# Arduino_pro_micro_sch.net
KiCad netlist of a schematic drawn in EasyEDA
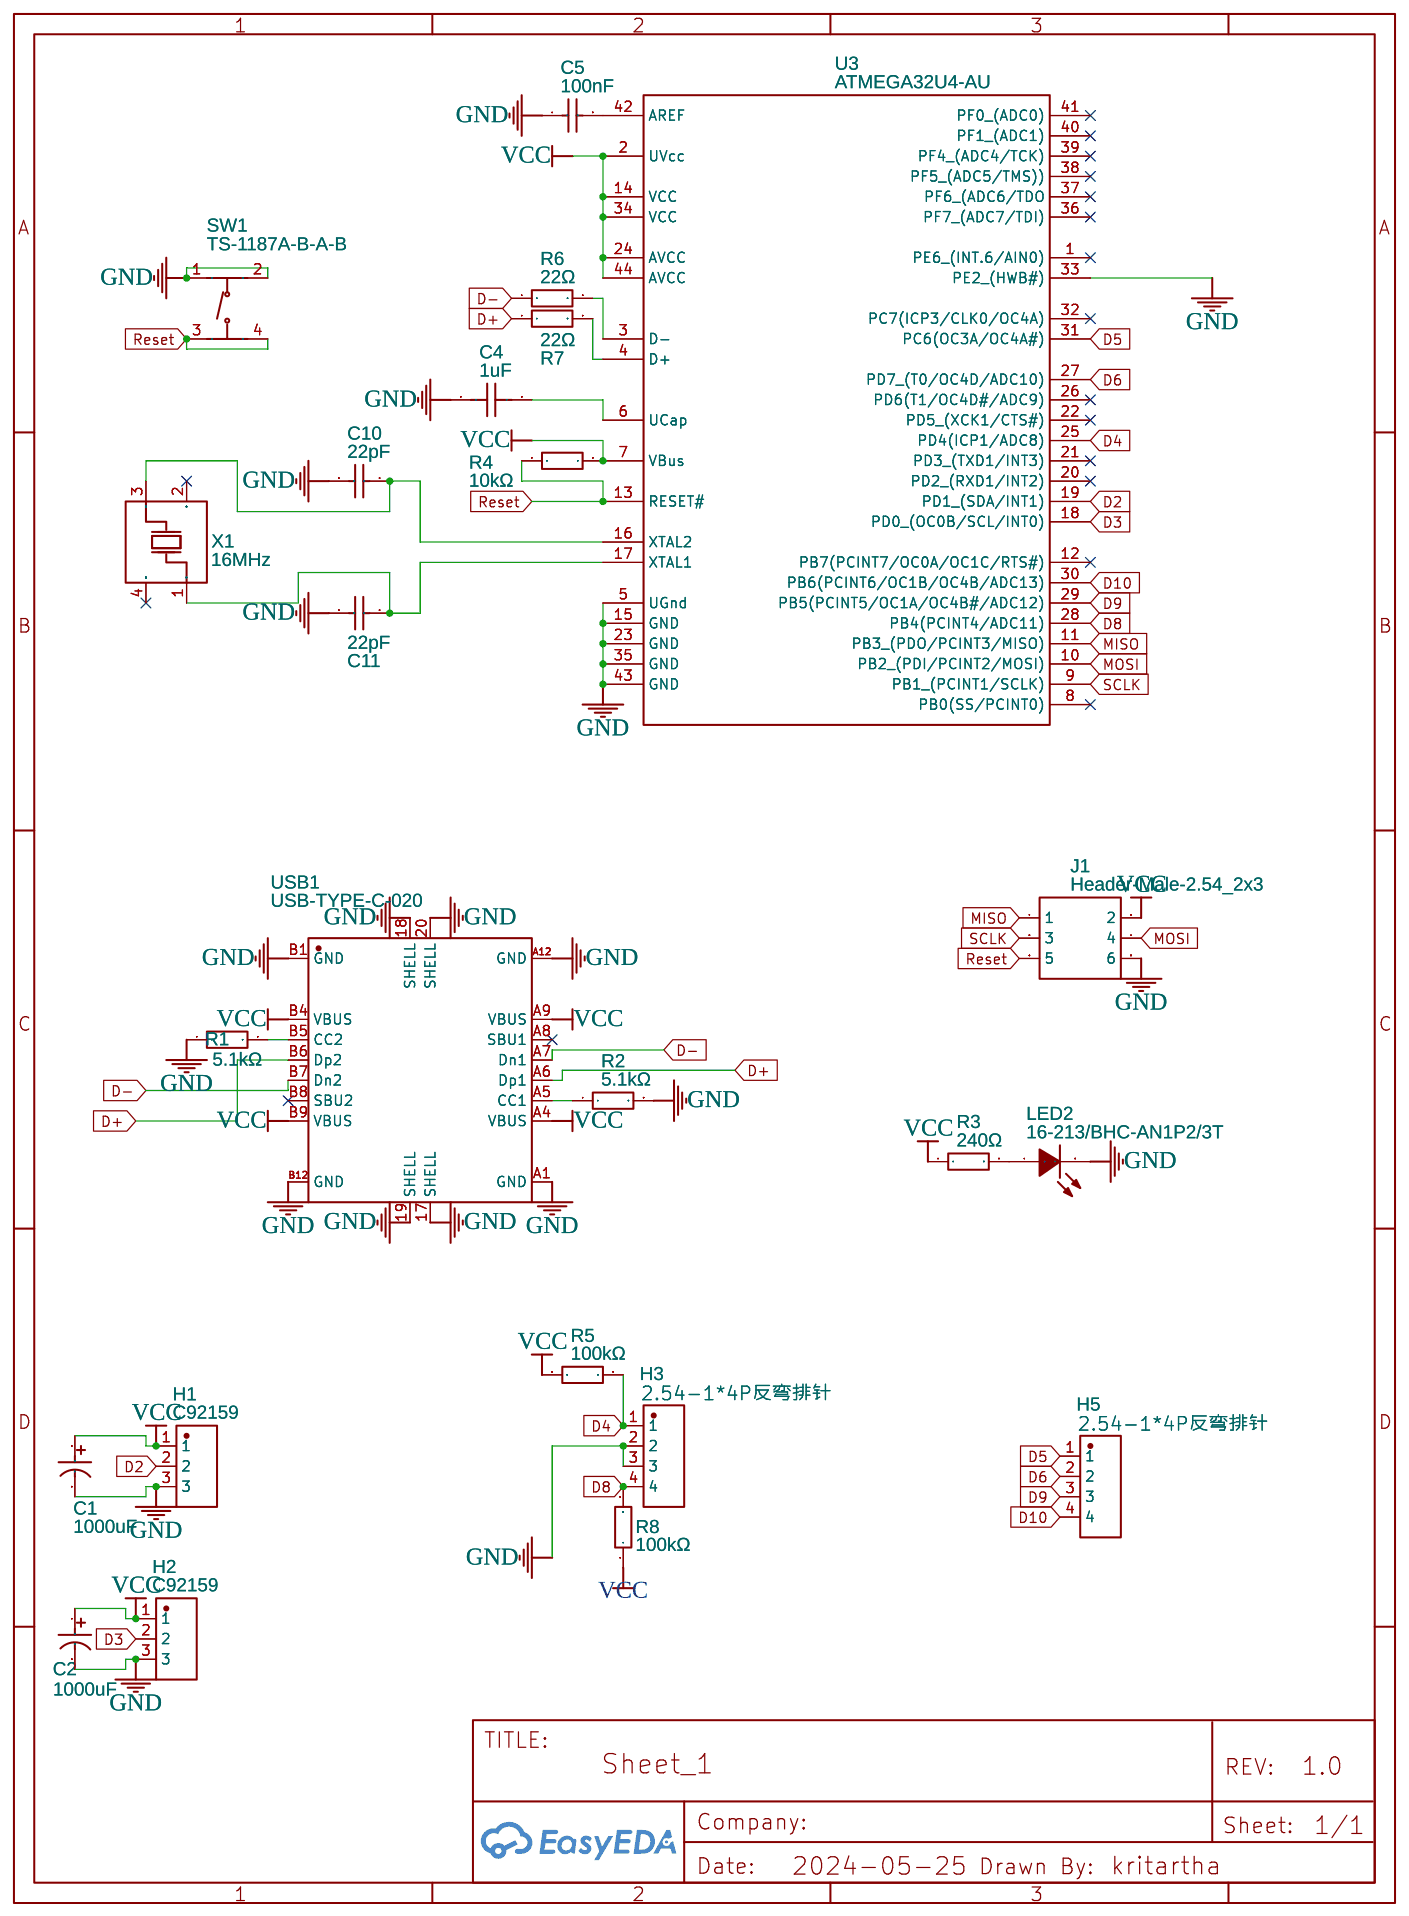
[diagram p0: schematic sheet]

(export (version "E")
  (design (tool "Eeschema 10.0.6"))
  (components
    (comp (ref "C1")
      (value "1000uF")
      (fields (field (name "Manufacturer Part") "RVT1C102M1010") (field (name "Manufacturer") "HONOR(荣誉)"))
      (libsource (lib "") (part "RVT1C102M1010_C3359"))
    )
    (comp (ref "C2")
      (value "1000uF")
      (fields (field (name "Manufacturer Part") "RVT1C102M1010") (field (name "Manufacturer") "HONOR(荣誉)"))
      (libsource (lib "") (part "RVT1C102M1010_C3359"))
    )
    (comp (ref "C4")
      (value "1uF")
      (fields
        (field (name "Manufacturer Part") "CL05A105KA5NQNC")
        (field (name "Manufacturer") "SAMSUNG(三星)")
      )
      (libsource (lib "") (part "CL05A105KA5NQNC"))
    )
    (comp (ref "C5")
      (value "100nF")
      (fields
        (field (name "Manufacturer Part") "CL05B104KO5NNNC")
        (field (name "Manufacturer") "SAMSUNG(三星)")
      )
      (libsource (lib "") (part "CL05B104KO5NNNC"))
    )
    (comp (ref "C10")
      (value "22pF")
      (fields (field (name "Manufacturer Part") "0402CG220J500NT") (field (name "Manufacturer") "FH(风华)"))
      (libsource (lib "") (part "0402CG220J500NT_1"))
    )
    (comp (ref "C11")
      (value "22pF")
      (fields (field (name "Manufacturer Part") "0402CG220J500NT") (field (name "Manufacturer") "FH(风华)"))
      (libsource (lib "") (part "0402CG220J500NT"))
    )
    (comp (ref "H1")
      (value "C92159")
      (fields (field (name "Manufacturer Part") "2.54-1*3P正弯针") (field (name "Manufacturer") "BOOMELE(博穆精密)"))
      (libsource (lib "") (part "C92159"))
    )
    (comp (ref "H2")
      (value "C92159")
      (fields (field (name "Manufacturer Part") "2.54-1*3P正弯针") (field (name "Manufacturer") "BOOMELE(博穆精密)"))
      (libsource (lib "") (part "C92159"))
    )
    (comp (ref "H3")
      (value "2.54-1*4P反弯排针")
      (fields (field (name "Manufacturer") "BOOMELE(博穆精密)"))
      (libsource (lib "") (part "2.54-1*4P反弯排针"))
    )
    (comp (ref "H5")
      (value "2.54-1*4P反弯排针")
      (fields (field (name "Manufacturer") "BOOMELE(博穆精密)"))
      (libsource (lib "") (part "2.54-1*4P反弯排针"))
    )
    (comp (ref "J1")
      (value "Header-Male-2.54_2x3")
      (fields (field (name "Manufacturer Part") "2.54-2*3P针") (field (name "Manufacturer") "BOOMELE(博穆精密)"))
      (libsource (lib "") (part "Header-Male-2.54_2x3"))
    )
    (comp (ref "LED2")
      (value "16-213/BHC-AN1P2/3T")
      (fields (field (name "Manufacturer") "EVERLIGHT(亿光)"))
      (libsource (lib "") (part "16-213/BHC-AN1P2/3T"))
    )
    (comp (ref "R1")
      (value "5.1kΩ")
      (fields
        (field (name "Manufacturer Part") "0402WGF5101TCE")
        (field (name "Manufacturer") "UNI-ROYAL(厚声)")
      )
      (libsource (lib "") (part "0402WGF5101TCE"))
    )
    (comp (ref "R2")
      (value "5.1kΩ")
      (fields
        (field (name "Manufacturer Part") "0402WGF5101TCE")
        (field (name "Manufacturer") "UNI-ROYAL(厚声)")
      )
      (libsource (lib "") (part "0402WGF5101TCE"))
    )
    (comp (ref "R3")
      (value "240Ω")
      (fields (field (name "Manufacturer Part") "RS-03K2400FT") (field (name "Manufacturer") "FH(风华)"))
      (libsource (lib "") (part "RS-03K2400FT"))
    )
    (comp (ref "R4")
      (value "10kΩ")
      (fields
        (field (name "Manufacturer Part") "0402WGF1002TCE")
        (field (name "Manufacturer") "UNI-ROYAL(厚声)")
      )
      (libsource (lib "") (part "0402WGF1002TCE"))
    )
    (comp (ref "R5")
      (value "100kΩ")
      (fields
        (field (name "Manufacturer Part") "0402WGF1003TCE")
        (field (name "Manufacturer") "UNI-ROYAL(厚声)")
      )
      (libsource (lib "") (part "0402WGF1003TCE"))
    )
    (comp (ref "R6")
      (value "22Ω")
      (fields
        (field (name "Manufacturer Part") "0402WGF220JTCE")
        (field (name "Manufacturer") "UNI-ROYAL(厚声)")
      )
      (libsource (lib "") (part "0402WGF220JTCE"))
    )
    (comp (ref "R7")
      (value "22Ω")
      (fields
        (field (name "Manufacturer Part") "0402WGF220JTCE")
        (field (name "Manufacturer") "UNI-ROYAL(厚声)")
      )
      (libsource (lib "") (part "0402WGF220JTCE"))
    )
    (comp (ref "R8")
      (value "100kΩ")
      (fields
        (field (name "Manufacturer Part") "0402WGF1003TCE")
        (field (name "Manufacturer") "UNI-ROYAL(厚声)")
      )
      (libsource (lib "") (part "0402WGF1003TCE_1"))
    )
    (comp (ref "SW1")
      (value "TS-1187A-B-A-B")
      (fields (field (name "Manufacturer") "XKB Connectivity(中国星坤)"))
      (libsource (lib "") (part "TS-1187A-B-A-B"))
    )
    (comp (ref "U3")
      (value "ATMEGA32U4-AU")
      (fields (field (name "Manufacturer") "MICROCHIP(美国微芯)"))
      (libsource (lib "") (part "ATMEGA32U4-AU"))
    )
    (comp (ref "USB1")
      (value "USB-TYPE-C-020")
      (fields (field (name "Manufacturer") "DEALON(德艺隆)"))
      (libsource (lib "") (part "USB-TYPE-C-020"))
    )
    (comp (ref "X1")
      (value "16MHz")
      (fields (field (name "Manufacturer Part") "X322516MLB4SI") (field (name "Manufacturer") "YXC(扬兴晶振)"))
      (libsource (lib "") (part "X322516MLB4SI"))
    )
  )
  (nets
    (net (code "1") (name "D+") (class "Default")
      (node (ref "R7") (pin "1") (pinfunction "1_1") (pintype "input"))
      (node (ref "USB1") (pin "A6") (pinfunction "Dp1_A6") (pintype "unspecified"))
      (node (ref "USB1") (pin "B6") (pinfunction "Dp2_B6") (pintype "unspecified"))
    )
    (net (code "2") (name "D-") (class "Default")
      (node (ref "R6") (pin "1") (pinfunction "1_1") (pintype "input"))
      (node (ref "USB1") (pin "A7") (pinfunction "Dn1_A7") (pintype "unspecified"))
      (node (ref "USB1") (pin "B7") (pinfunction "Dn2_B7") (pintype "unspecified"))
    )
    (net (code "3") (name "D2") (class "Default")
      (node (ref "H1") (pin "2") (pinfunction "2_2") (pintype "unspecified"))
      (node (ref "U3") (pin "19") (pinfunction "PD1_(SDA/INT1)_19") (pintype "bidirectional"))
    )
    (net (code "4") (name "D3") (class "Default")
      (node (ref "H2") (pin "2") (pinfunction "2_2") (pintype "unspecified"))
      (node (ref "U3") (pin "18") (pinfunction "PD0_(OC0B/SCL/INT0)_18") (pintype "bidirectional"))
    )
    (net (code "5") (name "D4") (class "Default")
      (node (ref "H3") (pin "1") (pinfunction "1_1") (pintype "unspecified"))
      (node (ref "R5") (pin "1") (pinfunction "1_1") (pintype "input"))
      (node (ref "U3") (pin "25") (pinfunction "PD4(ICP1/ADC8)_25") (pintype "bidirectional"))
    )
    (net (code "6") (name "D5") (class "Default")
      (node (ref "H5") (pin "1") (pinfunction "1_1") (pintype "unspecified"))
      (node (ref "U3") (pin "31") (pinfunction "PC6(OC3A/OC4A#)_31") (pintype "bidirectional"))
    )
    (net (code "7") (name "D6") (class "Default")
      (node (ref "H5") (pin "2") (pinfunction "2_2") (pintype "unspecified"))
      (node (ref "U3") (pin "27") (pinfunction "PD7_(T0/OC4D/ADC10)_27") (pintype "bidirectional"))
    )
    (net (code "8") (name "D8") (class "Default")
      (node (ref "H3") (pin "4") (pinfunction "4_4") (pintype "unspecified"))
      (node (ref "R8") (pin "2") (pinfunction "2_2") (pintype "input"))
      (node (ref "U3") (pin "28") (pinfunction "PB4(PCINT4/ADC11)_28") (pintype "bidirectional"))
    )
    (net (code "9") (name "D9") (class "Default")
      (node (ref "H5") (pin "3") (pinfunction "3_3") (pintype "unspecified"))
      (node (ref "U3") (pin "29") (pinfunction "PB5(PCINT5/OC1A/OC4B#/ADC12)_29") (pintype "bidirectional"))
    )
    (net (code "10") (name "D10") (class "Default")
      (node (ref "H5") (pin "4") (pinfunction "4_4") (pintype "unspecified"))
      (node (ref "U3") (pin "30") (pinfunction "PB6(PCINT6/OC1B/OC4B/ADC13)_30") (pintype "bidirectional"))
    )
    (net (code "11") (name "GND") (class "Default")
      (node (ref "C1") (pin "2") (pinfunction "2_2") (pintype "input"))
      (node (ref "C10") (pin "1") (pinfunction "1_1") (pintype "input"))
      (node (ref "C11") (pin "1") (pinfunction "1_1") (pintype "input"))
      (node (ref "C2") (pin "2") (pinfunction "2_2") (pintype "input"))
      (node (ref "C4") (pin "1") (pinfunction "1_1") (pintype "unspecified"))
      (node (ref "C5") (pin "1") (pinfunction "1_1") (pintype "input"))
      (node (ref "H1") (pin "3") (pinfunction "3_3") (pintype "unspecified"))
      (node (ref "H2") (pin "3") (pinfunction "3_3") (pintype "unspecified"))
      (node (ref "H3") (pin "2") (pinfunction "2_2") (pintype "unspecified"))
      (node (ref "H3") (pin "3") (pinfunction "3_3") (pintype "unspecified"))
      (node (ref "J1") (pin "6") (pinfunction "6_6") (pintype "input"))
      (node (ref "LED2") (pin "2") (pinfunction "K_2") (pintype "unspecified"))
      (node (ref "R1") (pin "1") (pinfunction "1_1") (pintype "input"))
      (node (ref "R2") (pin "2") (pinfunction "2_2") (pintype "input"))
      (node (ref "SW1") (pin "1") (pinfunction "A_1") (pintype "unspecified"))
      (node (ref "SW1") (pin "2") (pinfunction "B_2") (pintype "unspecified"))
      (node (ref "U3") (pin "15") (pinfunction "GND_15") (pintype "passive"))
      (node (ref "U3") (pin "23") (pinfunction "GND_23") (pintype "passive"))
      (node (ref "U3") (pin "33") (pinfunction "PE2_(HWB#)_33") (pintype "bidirectional"))
      (node (ref "U3") (pin "35") (pinfunction "GND_35") (pintype "passive"))
      (node (ref "U3") (pin "43") (pinfunction "GND_43") (pintype "passive"))
      (node (ref "U3") (pin "5") (pinfunction "UGnd_5") (pintype "passive"))
      (node (ref "USB1") (pin "17") (pinfunction "SHELL_17") (pintype "unspecified"))
      (node (ref "USB1") (pin "18") (pinfunction "SHELL_18") (pintype "unspecified"))
      (node (ref "USB1") (pin "19") (pinfunction "SHELL_19") (pintype "unspecified"))
      (node (ref "USB1") (pin "20") (pinfunction "SHELL_20") (pintype "unspecified"))
      (node (ref "USB1") (pin "A1") (pinfunction "GND_A1") (pintype "unspecified"))
      (node (ref "USB1") (pin "A12") (pinfunction "GND_A12") (pintype "unspecified"))
      (node (ref "USB1") (pin "B1") (pinfunction "GND_B1") (pintype "unspecified"))
      (node (ref "USB1") (pin "B12") (pinfunction "GND_B12") (pintype "unspecified"))
    )
    (net (code "12") (name "MISO") (class "Default")
      (node (ref "J1") (pin "1") (pinfunction "1_1") (pintype "input"))
      (node (ref "U3") (pin "11") (pinfunction "PB3_(PDO/PCINT3/MISO)_11") (pintype "bidirectional"))
    )
    (net (code "13") (name "MOSI") (class "Default")
      (node (ref "J1") (pin "4") (pinfunction "4_4") (pintype "input"))
      (node (ref "U3") (pin "10") (pinfunction "PB2_(PDI/PCINT2/MOSI)_10") (pintype "bidirectional"))
    )
    (net (code "14") (name "Net-(LED2-A)") (class "Default")
      (node (ref "LED2") (pin "1") (pinfunction "A_1") (pintype "unspecified"))
      (node (ref "R3") (pin "2") (pinfunction "2_2") (pintype "unspecified"))
    )
    (net (code "15") (name "Net-(U3-AREF)") (class "Default")
      (node (ref "C5") (pin "2") (pinfunction "2_2") (pintype "input"))
      (node (ref "U3") (pin "42") (pinfunction "AREF_42") (pintype "unspecified"))
    )
    (net (code "16") (name "Net-(U3-D+)") (class "Default")
      (node (ref "R7") (pin "2") (pinfunction "2_2") (pintype "input"))
      (node (ref "U3") (pin "4") (pinfunction "D+_4") (pintype "bidirectional"))
    )
    (net (code "17") (name "Net-(U3-D-)") (class "Default")
      (node (ref "R6") (pin "2") (pinfunction "2_2") (pintype "input"))
      (node (ref "U3") (pin "3") (pinfunction "D-_3") (pintype "bidirectional"))
    )
    (net (code "18") (name "Net-(U3-UCap)") (class "Default")
      (node (ref "C4") (pin "2") (pinfunction "2_2") (pintype "unspecified"))
      (node (ref "U3") (pin "6") (pinfunction "UCap_6") (pintype "unspecified"))
    )
    (net (code "19") (name "Net-(U3-XTAL1)") (class "Default")
      (node (ref "C11") (pin "2") (pinfunction "2_2") (pintype "input"))
      (node (ref "U3") (pin "17") (pinfunction "XTAL1_17") (pintype "unspecified"))
      (node (ref "X1") (pin "1") (pinfunction "OSC1_1") (pintype "unspecified"))
    )
    (net (code "20") (name "Net-(U3-XTAL2)") (class "Default")
      (node (ref "C10") (pin "2") (pinfunction "2_2") (pintype "input"))
      (node (ref "U3") (pin "16") (pinfunction "XTAL2_16") (pintype "output"))
      (node (ref "X1") (pin "3") (pinfunction "OSC2_3") (pintype "unspecified"))
    )
    (net (code "21") (name "Net-(USB1-CC1)") (class "Default")
      (node (ref "R2") (pin "1") (pinfunction "1_1") (pintype "input"))
      (node (ref "USB1") (pin "A5") (pinfunction "CC1_A5") (pintype "unspecified"))
    )
    (net (code "22") (name "Net-(USB1-CC2)") (class "Default")
      (node (ref "R1") (pin "2") (pinfunction "2_2") (pintype "input"))
      (node (ref "USB1") (pin "B5") (pinfunction "CC2_B5") (pintype "unspecified"))
    )
    (net (code "23") (name "Reset") (class "Default")
      (node (ref "J1") (pin "5") (pinfunction "5_5") (pintype "input"))
      (node (ref "R4") (pin "1") (pinfunction "1_1") (pintype "input"))
      (node (ref "SW1") (pin "3") (pinfunction "C_3") (pintype "unspecified"))
      (node (ref "SW1") (pin "4") (pinfunction "D_4") (pintype "unspecified"))
      (node (ref "U3") (pin "13") (pinfunction "RESET#_13") (pintype "unspecified"))
    )
    (net (code "24") (name "SCLK") (class "Default")
      (node (ref "J1") (pin "3") (pinfunction "3_3") (pintype "input"))
      (node (ref "U3") (pin "9") (pinfunction "PB1_(PCINT1/SCLK)_9") (pintype "bidirectional"))
    )
    (net (code "25") (name "VCC") (class "Default")
      (node (ref "C1") (pin "1") (pinfunction "1_1") (pintype "input"))
      (node (ref "C2") (pin "1") (pinfunction "1_1") (pintype "input"))
      (node (ref "H1") (pin "1") (pinfunction "1_1") (pintype "unspecified"))
      (node (ref "H2") (pin "1") (pinfunction "1_1") (pintype "unspecified"))
      (node (ref "J1") (pin "2") (pinfunction "2_2") (pintype "input"))
      (node (ref "R3") (pin "1") (pinfunction "1_1") (pintype "unspecified"))
      (node (ref "R4") (pin "2") (pinfunction "2_2") (pintype "input"))
      (node (ref "R5") (pin "2") (pinfunction "2_2") (pintype "input"))
      (node (ref "R8") (pin "1") (pinfunction "1_1") (pintype "input"))
      (node (ref "U3") (pin "14") (pinfunction "VCC_14") (pintype "passive"))
      (node (ref "U3") (pin "2") (pinfunction "UVcc_2") (pintype "passive"))
      (node (ref "U3") (pin "24") (pinfunction "AVCC_24") (pintype "passive"))
      (node (ref "U3") (pin "34") (pinfunction "VCC_34") (pintype "passive"))
      (node (ref "U3") (pin "44") (pinfunction "AVCC_44") (pintype "passive"))
      (node (ref "U3") (pin "7") (pinfunction "VBus_7") (pintype "unspecified"))
      (node (ref "USB1") (pin "A4") (pinfunction "VBUS_A4") (pintype "unspecified"))
      (node (ref "USB1") (pin "A9") (pinfunction "VBUS_A9") (pintype "unspecified"))
      (node (ref "USB1") (pin "B4") (pinfunction "VBUS_B4") (pintype "unspecified"))
      (node (ref "USB1") (pin "B9") (pinfunction "VBUS_B9") (pintype "unspecified"))
    )
    (net (code "26") (name "unconnected-(U3-PB0(SS{slash}PCINT0)-Pad8)") (class "Default")
      (node (ref "U3") (pin "8") (pinfunction "PB0(SS/PCINT0)_8") (pintype "bidirectional+no_connect"))
    )
    (net (code "27") (name "unconnected-(U3-PB7(PCINT7{slash}OC0A{slash}OC1C{slash}RTS#)-Pad12)") (class "Default")
      (node (ref "U3") (pin "12") (pinfunction "PB7(PCINT7/OC0A/OC1C/RTS#)_12") (pintype "bidirectional+no_connect"))
    )
    (net (code "28") (name "unconnected-(U3-PC7(ICP3{slash}CLK0{slash}OC4A)-Pad32)") (class "Default")
      (node (ref "U3") (pin "32") (pinfunction "PC7(ICP3/CLK0/OC4A)_32") (pintype "bidirectional+no_connect"))
    )
    (net (code "29") (name "unconnected-(U3-PD2_(RXD1{slash}INT2)-Pad20)") (class "Default")
      (node (ref "U3") (pin "20") (pinfunction "PD2_(RXD1/INT2)_20") (pintype "bidirectional+no_connect"))
    )
    (net (code "30") (name "unconnected-(U3-PD3_(TXD1{slash}INT3)-Pad21)") (class "Default")
      (node (ref "U3") (pin "21") (pinfunction "PD3_(TXD1/INT3)_21") (pintype "bidirectional+no_connect"))
    )
    (net (code "31") (name "unconnected-(U3-PD5_(XCK1{slash}CTS#)-Pad22)") (class "Default")
      (node (ref "U3") (pin "22") (pinfunction "PD5_(XCK1/CTS#)_22") (pintype "bidirectional+no_connect"))
    )
    (net (code "32") (name "unconnected-(U3-PD6(T1{slash}OC4D#{slash}ADC9)-Pad26)") (class "Default")
      (node (ref "U3") (pin "26") (pinfunction "PD6(T1/OC4D#/ADC9)_26") (pintype "bidirectional+no_connect"))
    )
    (net (code "33") (name "unconnected-(U3-PE6_(INT.6{slash}AIN0)-Pad1)") (class "Default")
      (node (ref "U3") (pin "1") (pinfunction "PE6_(INT.6/AIN0)_1") (pintype "bidirectional+no_connect"))
    )
    (net (code "34") (name "unconnected-(U3-PF0_(ADC0)-Pad41)") (class "Default")
      (node (ref "U3") (pin "41") (pinfunction "PF0_(ADC0)_41") (pintype "bidirectional+no_connect"))
    )
    (net (code "35") (name "unconnected-(U3-PF1_(ADC1)-Pad40)") (class "Default")
      (node (ref "U3") (pin "40") (pinfunction "PF1_(ADC1)_40") (pintype "bidirectional+no_connect"))
    )
    (net (code "36") (name "unconnected-(U3-PF4_(ADC4{slash}TCK)-Pad39)") (class "Default")
      (node (ref "U3") (pin "39") (pinfunction "PF4_(ADC4/TCK)_39") (pintype "bidirectional+no_connect"))
    )
    (net (code "37") (name "unconnected-(U3-PF5_(ADC5{slash}TMS))-Pad38)") (class "Default")
      (node (ref "U3") (pin "38") (pinfunction "PF5_(ADC5/TMS))_38") (pintype "bidirectional+no_connect"))
    )
    (net (code "38") (name "unconnected-(U3-PF6_(ADC6{slash}TDO-Pad37)") (class "Default")
      (node (ref "U3") (pin "37") (pinfunction "PF6_(ADC6/TDO_37") (pintype "bidirectional+no_connect"))
    )
    (net (code "39") (name "unconnected-(U3-PF7_(ADC7{slash}TDI)-Pad36)") (class "Default")
      (node (ref "U3") (pin "36") (pinfunction "PF7_(ADC7/TDI)_36") (pintype "bidirectional+no_connect"))
    )
    (net (code "40") (name "unconnected-(USB1-SBU1-PadA8)") (class "Default")
      (node (ref "USB1") (pin "A8") (pinfunction "SBU1_A8") (pintype "unspecified+no_connect"))
    )
    (net (code "41") (name "unconnected-(USB1-SBU2-PadB8)") (class "Default")
      (node (ref "USB1") (pin "B8") (pinfunction "SBU2_B8") (pintype "unspecified+no_connect"))
    )
    (net (code "42") (name "unconnected-(X1-GND-Pad2)") (class "Default")
      (node (ref "X1") (pin "2") (pinfunction "GND_2") (pintype "unspecified+no_connect"))
    )
    (net (code "43") (name "unconnected-(X1-GND-Pad4)") (class "Default")
      (node (ref "X1") (pin "4") (pinfunction "GND_4") (pintype "unspecified+no_connect"))
    )
  )
)
